# PR9019.net
KiCad netlist of a schematic drawn in EAGLE
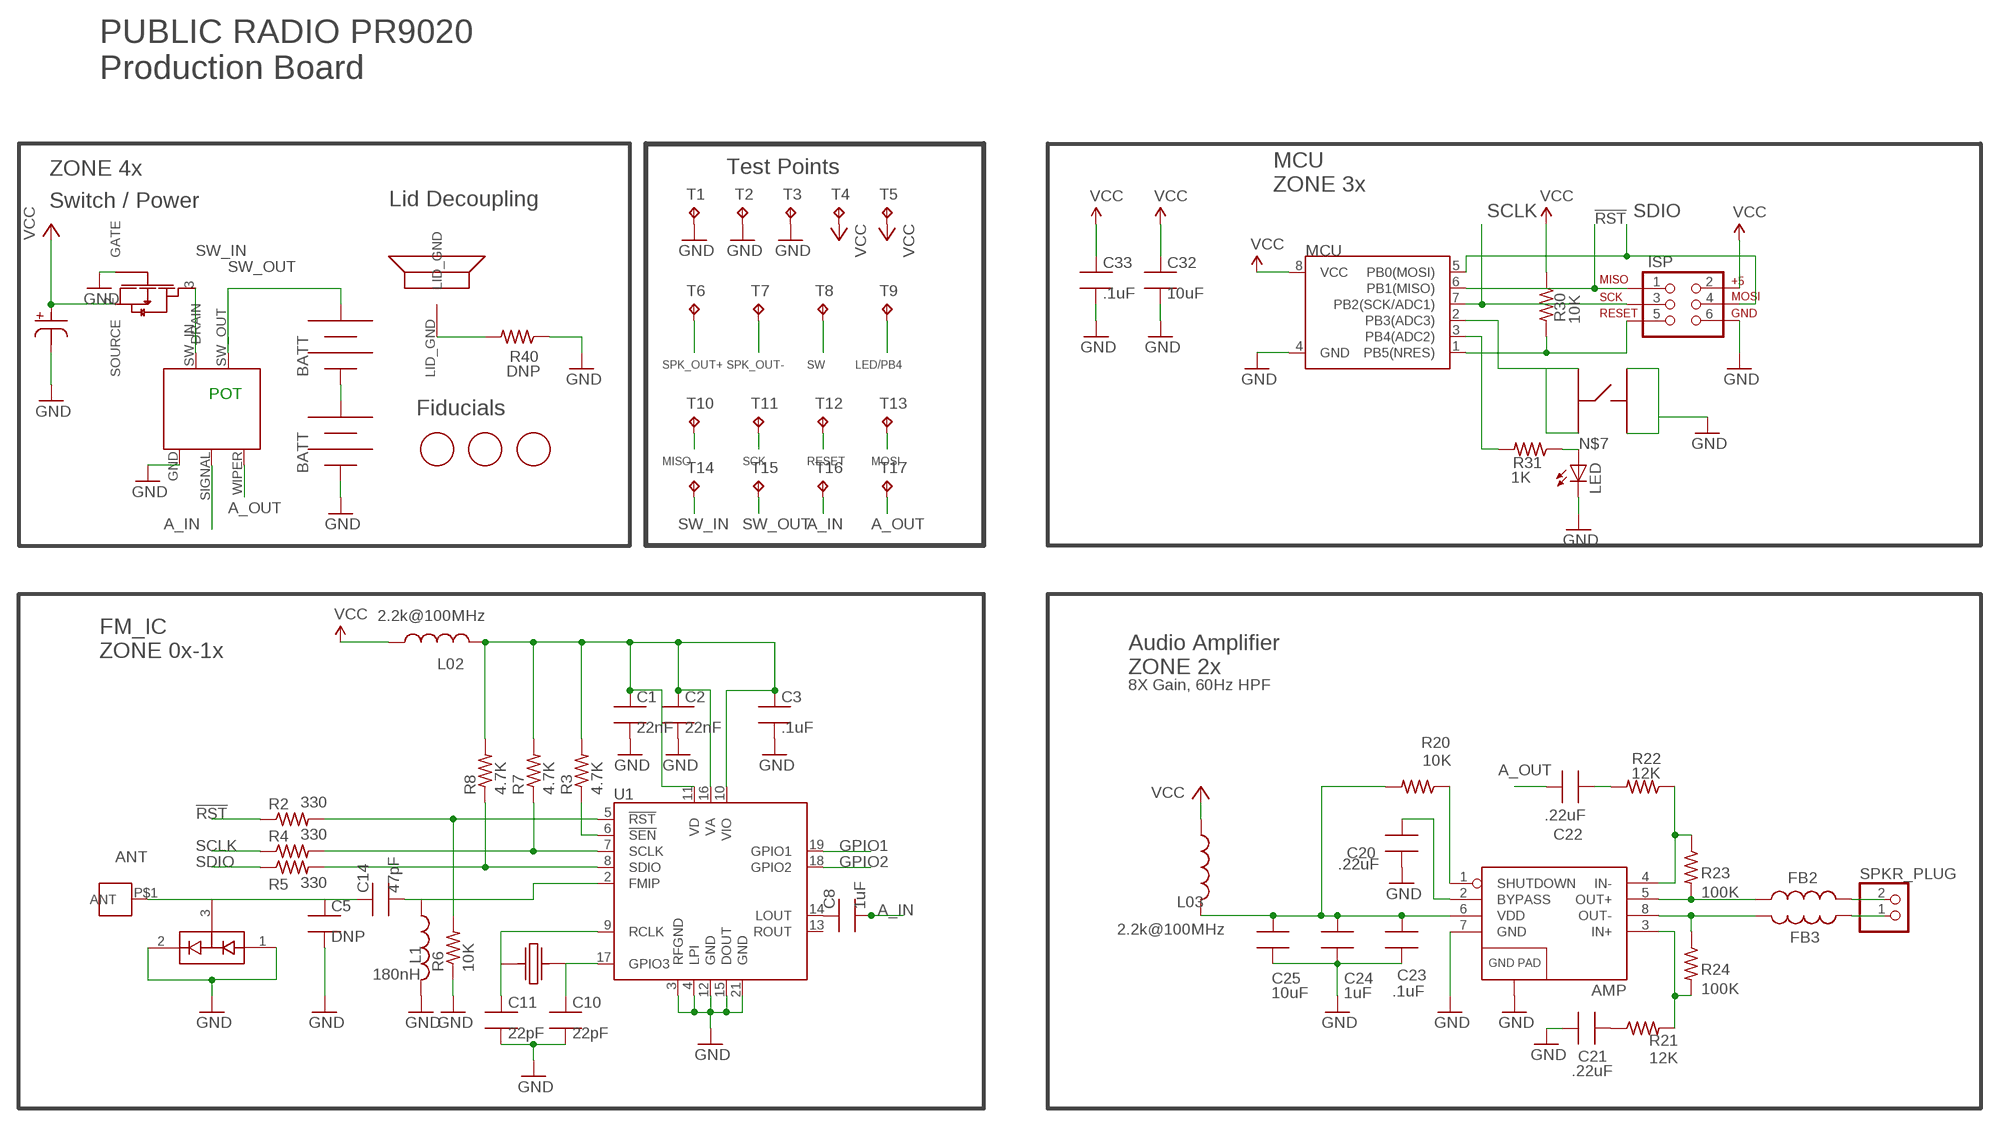
[diagram p0: schematic, sheet 1]

(export (version "E")
  (design (tool "Eeschema 10.0.6"))
  (components
    (comp (ref "AMP")
      (value "TPA6203A1")
      (footprint "eagle-import:8-MSOP")
      (libsource (lib "eagle-import") (part "TPA6203A1"))
    )
    (comp (ref "ANT_MOUNT")
      (value "DNP")
      (footprint "eagle-import:M3_BOLT_HOLE")
      (libsource (lib "eagle-import") (part "M3_SCREW_POST"))
    )
    (comp (ref "C1")
      (value "22nF")
      (footprint "eagle-import:0603_CPL")
      (fields
        (field (name "MFG_PN") "CL10B223KB8NNNC")
        (field (name "TOL") "10%")
        (field (name "VOLTAGE") "16V")
      )
      (libsource (lib "eagle-import") (part "C_SMT_0603_CPL"))
    )
    (comp (ref "C2")
      (value "22nF")
      (footprint "eagle-import:0603_CPL")
      (fields
        (field (name "MFG_PN") "CL10B223KB8NNNC")
        (field (name "TOL") "10%")
        (field (name "VOLTAGE") "16V")
      )
      (libsource (lib "eagle-import") (part "C_SMT_0603_CPL"))
    )
    (comp (ref "C3")
      (value ".1uF")
      (footprint "eagle-import:0603_CPL")
      (fields
        (field (name "MFG_PN") "CL10B104KB8SFNC")
        (field (name "TOL") "10%")
        (field (name "VOLTAGE") "16V")
      )
      (libsource (lib "eagle-import") (part "C_SMT_0603_CPL"))
    )
    (comp (ref "C5")
      (value "DNP")
      (footprint "eagle-import:0603_CPL")
      (fields (field (name "MFG_PN") "DNP") (field (name "TOL") "2%") (field (name "VOLTAGE") "50V"))
      (libsource (lib "eagle-import") (part "C_SMT_0603_CPL"))
    )
    (comp (ref "C8")
      (value "1uF")
      (footprint "eagle-import:0603_CPL")
      (fields
        (field (name "MFG_PN") "CL10B105KP8NNNC")
        (field (name "TOL") "10%")
        (field (name "VOLTAGE") "10V")
      )
      (libsource (lib "eagle-import") (part "C_SMT_0603_CPL"))
    )
    (comp (ref "C10")
      (value "22pF")
      (footprint "eagle-import:0603_CPL")
      (fields
        (field (name "MFG_PN") "C1608C0G1H220J080AA")
        (field (name "TOL") "5%")
        (field (name "VOLTAGE") "50V")
      )
      (libsource (lib "eagle-import") (part "C_SMT_0603_CPL"))
    )
    (comp (ref "C11")
      (value "22pF")
      (footprint "eagle-import:0603_CPL")
      (fields
        (field (name "MFG_PN") "C1608C0G1H220J080AA")
        (field (name "TOL") "5%")
        (field (name "VOLTAGE") "50V")
      )
      (libsource (lib "eagle-import") (part "C_SMT_0603_CPL"))
    )
    (comp (ref "C14")
      (value "47pF")
      (footprint "eagle-import:0603_CPL")
      (fields
        (field (name "MFG_PN") "CL10C470JB8NCNC")
        (field (name "TOL") "5%")
        (field (name "VOLTAGE") "50V")
      )
      (libsource (lib "eagle-import") (part "C_SMT_0603_CPL"))
    )
    (comp (ref "C20")
      (value ".22uF")
      (footprint "eagle-import:0603_CPL")
      (fields
        (field (name "MFG_PN") "C1608X7R1C224K080AC")
        (field (name "TOL") "10%")
        (field (name "VOLTAGE") "16V")
      )
      (libsource (lib "eagle-import") (part "C_SMT_0603_CPL"))
    )
    (comp (ref "C21")
      (value ".22uF")
      (footprint "eagle-import:0603_CPL")
      (fields
        (field (name "MFG_PN") "C1608X7R1C224K080AC")
        (field (name "TOL") "10%")
        (field (name "VOLTAGE") "16V")
      )
      (libsource (lib "eagle-import") (part "C_SMT_0603_CPL"))
    )
    (comp (ref "C22")
      (value ".22uF")
      (footprint "eagle-import:0603_CPL")
      (fields
        (field (name "MFG_PN") "C1608X7R1C224K080AC")
        (field (name "TOL") "10%")
        (field (name "VOLTAGE") "16V")
      )
      (libsource (lib "eagle-import") (part "C_SMT_0603_CPL"))
    )
    (comp (ref "C23")
      (value ".1uF")
      (footprint "eagle-import:0603_CPL")
      (fields
        (field (name "MFG_PN") "CL10B104KB8SFNC")
        (field (name "TOL") "10%")
        (field (name "VOLTAGE") "16V")
      )
      (libsource (lib "eagle-import") (part "C_SMT_0603_CPL"))
    )
    (comp (ref "C24")
      (value "1uF")
      (footprint "eagle-import:0603_CPL")
      (fields
        (field (name "MFG_PN") "CL10B105KP8NNNC")
        (field (name "TOL") "10%")
        (field (name "VOLTAGE") "10V")
      )
      (libsource (lib "eagle-import") (part "C_SMT_0603_CPL"))
    )
    (comp (ref "C25")
      (value "10uF")
      (footprint "eagle-import:0603_CPL")
      (fields
        (field (name "MFG_PN") "CL10A106MQ8NNNC")
        (field (name "TOL") "20%")
        (field (name "VOLTAGE") "6.3V")
      )
      (libsource (lib "eagle-import") (part "C_SMT_0603_CPL"))
    )
    (comp (ref "C32")
      (value "10uF")
      (footprint "eagle-import:0603_CPL")
      (fields
        (field (name "MFG_PN") "CL10A106MQ8NNNC")
        (field (name "TOL") "20%")
        (field (name "VOLTAGE") "6.3V")
      )
      (libsource (lib "eagle-import") (part "C_SMT_0603_CPL"))
    )
    (comp (ref "C33")
      (value ".1uF")
      (footprint "eagle-import:0603_CPL")
      (fields
        (field (name "MFG_PN") "CL10B104KB8SFNC")
        (field (name "TOL") "10%")
        (field (name "VOLTAGE") "16V")
      )
      (libsource (lib "eagle-import") (part "C_SMT_0603_CPL"))
    )
    (comp (ref "C40")
      (value "220uF")
      (footprint "eagle-import:NICHICON_UD_63")
      (fields (field (name "TOL") "20%") (field (name "VOLTAGE") "16V"))
      (libsource (lib "eagle-import") (part "NICHICON_SERIESUD"))
    )
    (comp (ref "D1")
      (value "BAV99")
      (footprint "eagle-import:SOT23_CPL")
      (fields (field (name "MFG_PN") "BAV99,215"))
      (libsource (lib "eagle-import") (part "BAV99"))
    )
    (comp (ref "FB2")
      (value "L_SMT_0805_ADAFRUIT")
      (footprint "eagle-import:0805_ADAFRUIT")
      (fields
        (field (name "CURRENT") "2A")
        (field (name "DCR") "45m")
        (field (name "MFG_PN") "HI0805R800R-10")
      )
      (libsource (lib "eagle-import") (part "L_SMT_0805_ADAFRUIT"))
    )
    (comp (ref "FB3")
      (value "L_SMT_0805_ADAFRUIT")
      (footprint "eagle-import:0805_ADAFRUIT")
      (fields
        (field (name "CURRENT") "2A")
        (field (name "DCR") "45m")
        (field (name "MFG_PN") "HI0805R800R-10")
      )
      (libsource (lib "eagle-import") (part "L_SMT_0805_ADAFRUIT"))
    )
    (comp (ref "FET1")
      (value "AO3435")
      (footprint "eagle-import:SOT23_CPL")
      (fields (field (name "MFG_PN") "AO3435"))
      (libsource (lib "eagle-import") (part "AO3435"))
    )
    (comp (ref "ISP")
      (value "AVR_SPI_PRG_6NS")
      (footprint "eagle-import:2X3-NS")
      (libsource (lib "eagle-import") (part "AVR_SPI_PRG_6NS"))
    )
    (comp (ref "JP5")
      (value "BK-92_MPD_AA_BATT_CLIP")
      (footprint "eagle-import:BK92_AA_BATT")
      (fields (field (name "MFG_PN") "2 of BK92 - supplied by CL Labs"))
      (libsource (lib "eagle-import") (part "BK-92_MPD_AA_BATT_CLIP"))
    )
    (comp (ref "JP6")
      (value "BK-92_MPD_AA_BATT_CLIP")
      (footprint "eagle-import:BK92_AA_BATT")
      (fields (field (name "MFG_PN") "2 of BK92 - supplied by CL Labs"))
      (libsource (lib "eagle-import") (part "BK-92_MPD_AA_BATT_CLIP"))
    )
    (comp (ref "L1")
      (value "180nH")
      (footprint "eagle-import:0805_ADAFRUIT")
      (fields
        (field (name "CURRENT") "400mA")
        (field (name "DCR") "640m")
        (field (name "MFG_PN") "AISC-0805-R18J-T")
        (field (name "TOL") "5%")
      )
      (libsource (lib "eagle-import") (part "L_SMT_0805_ADAFRUIT"))
    )
    (comp (ref "L02")
      (value "2.2k@100MHz")
      (footprint "eagle-import:0603_CPL")
      (fields
        (field (name "CURRENT") "150mA")
        (field (name "DCR") "2.3")
        (field (name "MFG_PN") "HZ0603A222R-10")
      )
      (libsource (lib "eagle-import") (part "L_SMT_0603_CPL"))
    )
    (comp (ref "L03")
      (value "2.2k@100MHz")
      (footprint "eagle-import:0603_CPL")
      (fields
        (field (name "CURRENT") "150mA")
        (field (name "DCR") "2.3")
        (field (name "MFG_PN") "HZ0603A222R-10")
      )
      (libsource (lib "eagle-import") (part "L_SMT_0603_CPL"))
    )
    (comp (ref "LED")
      (value "LEDCHIPLED_0805")
      (footprint "eagle-import:CHIPLED_0805")
      (libsource (lib "eagle-import") (part "LEDCHIPLED_0805"))
    )
    (comp (ref "MARK1")
      (value "FIDUCIAL")
      (footprint "eagle-import:FIDUCIAL_1MM")
      (libsource (lib "eagle-import") (part "FIDUCIAL"))
    )
    (comp (ref "MARK2")
      (value "FIDUCIAL")
      (footprint "eagle-import:FIDUCIAL_1MM")
      (libsource (lib "eagle-import") (part "FIDUCIAL"))
    )
    (comp (ref "MARK3")
      (value "FIDUCIAL")
      (footprint "eagle-import:FIDUCIAL_1MM")
      (libsource (lib "eagle-import") (part "FIDUCIAL"))
    )
    (comp (ref "MCU")
      (value "ATTINY45TINY45-20-SMT")
      (footprint "eagle-import:8-SOIC")
      (libsource (lib "eagle-import") (part "ATTINY45TINY45-20-SMT"))
    )
    (comp (ref "R1")
      (value "RV170SF_TAIWANA_POT_SW")
      (footprint "eagle-import:RV170SF_SW_POT")
      (fields (field (name "MFG_PN") "RV170SF-43-20F-A10K - supplied by CL Labs"))
      (libsource (lib "eagle-import") (part "RV170SF_TAIWANA_POT_SW"))
    )
    (comp (ref "R2")
      (value "330")
      (footprint "eagle-import:0603_CPL")
      (fields (field (name "MFG_PN") "MCR03ERTJ331") (field (name "POWER") "1/10W") (field (name "TOL") "5%"))
      (libsource (lib "eagle-import") (part "R_SMT_R0603_CPL"))
    )
    (comp (ref "R3")
      (value "4.7K")
      (footprint "eagle-import:0603_CPL")
      (fields
        (field (name "MFG_PN") "ERJ-3EKF4701V")
        (field (name "POWER") "1/10W")
        (field (name "TOL") "1%")
      )
      (libsource (lib "eagle-import") (part "R_SMT_R0603_CPL"))
    )
    (comp (ref "R4")
      (value "330")
      (footprint "eagle-import:0603_CPL")
      (fields (field (name "MFG_PN") "MCR03ERTJ331") (field (name "POWER") "1/10W") (field (name "TOL") "5%"))
      (libsource (lib "eagle-import") (part "R_SMT_R0603_CPL"))
    )
    (comp (ref "R5")
      (value "330")
      (footprint "eagle-import:0603_CPL")
      (fields (field (name "MFG_PN") "MCR03ERTJ331") (field (name "POWER") "1/10W") (field (name "TOL") "5%"))
      (libsource (lib "eagle-import") (part "R_SMT_R0603_CPL"))
    )
    (comp (ref "R6")
      (value "10K")
      (footprint "eagle-import:0603_CPL")
      (fields
        (field (name "MFG_PN") "ERJ-3GEYJ103V")
        (field (name "POWER") "1/10W")
        (field (name "TOL") "5%")
      )
      (libsource (lib "eagle-import") (part "R_SMT_R0603_CPL"))
    )
    (comp (ref "R7")
      (value "4.7K")
      (footprint "eagle-import:0603_CPL")
      (fields
        (field (name "MFG_PN") "ERJ-3EKF4701V")
        (field (name "POWER") "1/10W")
        (field (name "TOL") "1%")
      )
      (libsource (lib "eagle-import") (part "R_SMT_R0603_CPL"))
    )
    (comp (ref "R8")
      (value "4.7K")
      (footprint "eagle-import:0603_CPL")
      (fields
        (field (name "MFG_PN") "ERJ-3EKF4701V")
        (field (name "POWER") "1/10W")
        (field (name "TOL") "1%")
      )
      (libsource (lib "eagle-import") (part "R_SMT_R0603_CPL"))
    )
    (comp (ref "R20")
      (value "10K")
      (footprint "eagle-import:0603_CPL")
      (fields
        (field (name "MFG_PN") "ERJ-3GEYJ103V")
        (field (name "POWER") "1/10W")
        (field (name "TOL") "5%")
      )
      (libsource (lib "eagle-import") (part "R_SMT_R0603_CPL"))
    )
    (comp (ref "R21")
      (value "12K")
      (footprint "eagle-import:0603_CPL")
      (fields
        (field (name "MFG_PN") "RC0603FR-0712KL")
        (field (name "POWER") "1/10W")
        (field (name "TOL") "1%")
      )
      (libsource (lib "eagle-import") (part "R_SMT_R0603_CPL"))
    )
    (comp (ref "R22")
      (value "12K")
      (footprint "eagle-import:0603_CPL")
      (fields
        (field (name "MFG_PN") "RC0603FR-0712KL")
        (field (name "POWER") "1/10W")
        (field (name "TOL") "1%")
      )
      (libsource (lib "eagle-import") (part "R_SMT_R0603_CPL"))
    )
    (comp (ref "R23")
      (value "100K")
      (footprint "eagle-import:0603_CPL")
      (fields
        (field (name "MFG_PN") "ERJ-3EKF1003V")
        (field (name "POWER") "1/10W")
        (field (name "TOL") "1%")
      )
      (libsource (lib "eagle-import") (part "R_SMT_R0603_CPL"))
    )
    (comp (ref "R24")
      (value "100K")
      (footprint "eagle-import:0603_CPL")
      (fields
        (field (name "MFG_PN") "ERJ-3EKF1003V")
        (field (name "POWER") "1/10W")
        (field (name "TOL") "1%")
      )
      (libsource (lib "eagle-import") (part "R_SMT_R0603_CPL"))
    )
    (comp (ref "R30")
      (value "10K")
      (footprint "eagle-import:0603_CPL")
      (fields
        (field (name "MFG_PN") "ERJ-3GEYJ103V")
        (field (name "POWER") "1/10W")
        (field (name "TOL") "5%")
      )
      (libsource (lib "eagle-import") (part "R_SMT_R0603_CPL"))
    )
    (comp (ref "R31")
      (value "1K")
      (footprint "eagle-import:0603_CPL")
      (fields
        (field (name "MFG_PN") "ERJ-3EKF1001V")
        (field (name "POWER") "1/10W")
        (field (name "TOL") "1%")
      )
      (libsource (lib "eagle-import") (part "R_SMT_R0603_CPL"))
    )
    (comp (ref "R40")
      (value "DNP")
      (footprint "eagle-import:0603_CPL")
      (fields (field (name "MFG_PN") "ERJ-3GEY0R00V"))
      (libsource (lib "eagle-import") (part "R_SMT_R0603_CPL"))
    )
    (comp (ref "SPKR_PLACE")
      (value "DNP")
      (footprint "eagle-import:PR2023_SPKR_PLACE")
      (libsource (lib "eagle-import") (part "PR2023_SPKR"))
    )
    (comp (ref "SPKR_PLUG")
      (value "JST_2PIN-SMT-RA")
      (footprint "eagle-import:JST-B2B-PH-SM4-TB")
      (libsource (lib "eagle-import") (part "JST_2PIN-SMT-RA"))
    )
    (comp (ref "SW1")
      (value "C&K_PTS645")
      (footprint "eagle-import:C&K_PTS645_SMT")
      (libsource (lib "eagle-import") (part "C&K_PTS645"))
    )
    (comp (ref "T1")
      (value "TPTP20R")
      (footprint "eagle-import:TP20R")
      (libsource (lib "eagle-import") (part "TPTP20R"))
    )
    (comp (ref "T2")
      (value "TPTP20R")
      (footprint "eagle-import:TP20R")
      (libsource (lib "eagle-import") (part "TPTP20R"))
    )
    (comp (ref "T3")
      (value "TPTP20R")
      (footprint "eagle-import:TP20R")
      (libsource (lib "eagle-import") (part "TPTP20R"))
    )
    (comp (ref "T4")
      (value "TPTP20R")
      (footprint "eagle-import:TP20R")
      (libsource (lib "eagle-import") (part "TPTP20R"))
    )
    (comp (ref "T5")
      (value "TPTP20R")
      (footprint "eagle-import:TP20R")
      (libsource (lib "eagle-import") (part "TPTP20R"))
    )
    (comp (ref "T6")
      (value "TPTP20R")
      (footprint "eagle-import:TP20R")
      (libsource (lib "eagle-import") (part "TPTP20R"))
    )
    (comp (ref "T7")
      (value "TPTP20R")
      (footprint "eagle-import:TP20R")
      (libsource (lib "eagle-import") (part "TPTP20R"))
    )
    (comp (ref "T8")
      (value "TPTP20R")
      (footprint "eagle-import:TP20R")
      (libsource (lib "eagle-import") (part "TPTP20R"))
    )
    (comp (ref "T9")
      (value "TPTP20R")
      (footprint "eagle-import:TP20R")
      (libsource (lib "eagle-import") (part "TPTP20R"))
    )
    (comp (ref "T10")
      (value "TPTP20R")
      (footprint "eagle-import:TP20R")
      (libsource (lib "eagle-import") (part "TPTP20R"))
    )
    (comp (ref "T11")
      (value "TPTP20R")
      (footprint "eagle-import:TP20R")
      (libsource (lib "eagle-import") (part "TPTP20R"))
    )
    (comp (ref "T12")
      (value "TPTP20R")
      (footprint "eagle-import:TP20R")
      (libsource (lib "eagle-import") (part "TPTP20R"))
    )
    (comp (ref "T13")
      (value "TPTP20R")
      (footprint "eagle-import:TP20R")
      (libsource (lib "eagle-import") (part "TPTP20R"))
    )
    (comp (ref "T14")
      (value "TPTP20R")
      (footprint "eagle-import:TP20R")
      (libsource (lib "eagle-import") (part "TPTP20R"))
    )
    (comp (ref "T15")
      (value "TPTP20R")
      (footprint "eagle-import:TP20R")
      (libsource (lib "eagle-import") (part "TPTP20R"))
    )
    (comp (ref "T16")
      (value "TPTP20R")
      (footprint "eagle-import:TP20R")
      (libsource (lib "eagle-import") (part "TPTP20R"))
    )
    (comp (ref "T17")
      (value "TPTP20R")
      (footprint "eagle-import:TP20R")
      (libsource (lib "eagle-import") (part "TPTP20R"))
    )
    (comp (ref "U1")
      (value "SI4702-C19-GMR")
      (footprint "eagle-import:SI470X_20_QFN")
      (fields (field (name "MFG_PN") "Si4702 C19 GM - supplied by CL Labs"))
      (libsource (lib "eagle-import") (part "SI4702-C19-GMR"))
    )
    (comp (ref "X1")
      (value "ABS25XTAL")
      (footprint "eagle-import:4-SOJ")
      (libsource (lib "eagle-import") (part "ABS25XTAL"))
    )
  )
  (nets
    (net (code "1") (name "/ANT") (class "Default")
      (node (ref "ANT_MOUNT") (pin "P$1") (pinfunction "ANT_P$1") (pintype "bidirectional"))
      (node (ref "C14") (pin "1") (pinfunction "1_1") (pintype "passive"))
      (node (ref "C5") (pin "1") (pinfunction "1_1") (pintype "passive"))
      (node (ref "D1") (pin "3") (pinfunction "COM_3") (pintype "bidirectional"))
    )
    (net (code "2") (name "/A_IN") (class "Default")
      (node (ref "C8") (pin "2") (pinfunction "2_2") (pintype "passive"))
      (node (ref "R1") (pin "SIGNAL") (pinfunction "SIGNAL_SIGNAL") (pintype "bidirectional"))
      (node (ref "T16") (pin "TP") (pinfunction "TP_TP") (pintype "input"))
    )
    (net (code "3") (name "/A_OUT") (class "Default")
      (node (ref "C22") (pin "2") (pinfunction "2_2") (pintype "passive"))
      (node (ref "R1") (pin "WIPER") (pinfunction "WIPER_WIPER") (pintype "bidirectional"))
      (node (ref "T17") (pin "TP") (pinfunction "TP_TP") (pintype "input"))
    )
    (net (code "4") (name "/GPIO1") (class "Default")
      (node (ref "U1") (pin "19") (pinfunction "GPIO1_19") (pintype "bidirectional"))
    )
    (net (code "5") (name "/GPIO2") (class "Default")
      (node (ref "U1") (pin "18") (pinfunction "GPIO2_18") (pintype "bidirectional"))
    )
    (net (code "6") (name "/LED{slash}PB4") (class "Default")
      (node (ref "MCU") (pin "3") (pinfunction "PB4(ADC2)_3") (pintype "bidirectional"))
      (node (ref "R31") (pin "2") (pinfunction "2_2") (pintype "passive"))
      (node (ref "T9") (pin "TP") (pinfunction "TP_TP") (pintype "input"))
    )
    (net (code "7") (name "/N$7") (class "Default")
      (node (ref "LED") (pin "A") (pinfunction "A_A") (pintype "passive"))
      (node (ref "R31") (pin "1") (pinfunction "1_1") (pintype "passive"))
    )
    (net (code "8") (name "/RESET") (class "Default")
      (node (ref "ISP") (pin "5") (pinfunction "5_5") (pintype "passive"))
      (node (ref "MCU") (pin "1") (pinfunction "PB5(NRES)_1") (pintype "bidirectional"))
      (node (ref "R30") (pin "2") (pinfunction "2_2") (pintype "passive"))
      (node (ref "T12") (pin "TP") (pinfunction "TP_TP") (pintype "input"))
    )
    (net (code "9") (name "/SCLK") (class "Default")
      (node (ref "ISP") (pin "3") (pinfunction "3_3") (pintype "passive"))
      (node (ref "MCU") (pin "7") (pinfunction "PB2(SCK/ADC1)_7") (pintype "bidirectional"))
      (node (ref "R4") (pin "1") (pinfunction "1_1") (pintype "passive"))
      (node (ref "T11") (pin "TP") (pinfunction "TP_TP") (pintype "input"))
    )
    (net (code "10") (name "/SDIO") (class "Default")
      (node (ref "ISP") (pin "4") (pinfunction "4_4") (pintype "passive"))
      (node (ref "MCU") (pin "5") (pinfunction "PB0(MOSI)_5") (pintype "bidirectional"))
      (node (ref "R5") (pin "1") (pinfunction "1_1") (pintype "passive"))
      (node (ref "T13") (pin "TP") (pinfunction "TP_TP") (pintype "input"))
    )
    (net (code "11") (name "/SPK_OUT+") (class "Default")
      (node (ref "FB2") (pin "2") (pinfunction "2_2") (pintype "passive"))
      (node (ref "SPKR_PLUG") (pin "2") (pinfunction "1_2") (pintype "passive"))
      (node (ref "T6") (pin "TP") (pinfunction "TP_TP") (pintype "input"))
    )
    (net (code "12") (name "/SPK_OUT-") (class "Default")
      (node (ref "FB3") (pin "1") (pinfunction "1_1") (pintype "passive"))
      (node (ref "SPKR_PLUG") (pin "1") (pinfunction "2_1") (pintype "passive"))
      (node (ref "T7") (pin "TP") (pinfunction "TP_TP") (pintype "input"))
    )
    (net (code "13") (name "/SW") (class "Default")
      (node (ref "MCU") (pin "2") (pinfunction "PB3(ADC3)_2") (pintype "bidirectional"))
      (node (ref "SW1") (pin "P$3") (pinfunction "P$3_P$3") (pintype "bidirectional"))
      (node (ref "SW1") (pin "P$4") (pinfunction "P$4_P$4") (pintype "bidirectional"))
      (node (ref "T8") (pin "TP") (pinfunction "TP_TP") (pintype "input"))
    )
    (net (code "14") (name "/SW_IN") (class "Default")
      (node (ref "FET1") (pin "3") (pinfunction "DRAIN_3") (pintype "bidirectional"))
      (node (ref "R1") (pin "SW_IN") (pinfunction "SW_IN_SW_IN") (pintype "bidirectional"))
      (node (ref "T14") (pin "TP") (pinfunction "TP_TP") (pintype "input"))
    )
    (net (code "15") (name "/SW_OUT") (class "Default")
      (node (ref "JP5") (pin "POS") (pinfunction "POS_POS") (pintype "bidirectional"))
      (node (ref "JP5") (pin "POS@2") (pinfunction "POS_POS@2") (pintype "bidirectional"))
      (node (ref "R1") (pin "SW_OUT") (pinfunction "SW_OUT_SW_OUT") (pintype "bidirectional"))
      (node (ref "T15") (pin "TP") (pinfunction "TP_TP") (pintype "input"))
    )
    (net (code "16") (name "/~{RST}") (class "Default")
      (node (ref "ISP") (pin "1") (pinfunction "1_1") (pintype "passive"))
      (node (ref "MCU") (pin "6") (pinfunction "PB1(MISO)_6") (pintype "bidirectional"))
      (node (ref "R2") (pin "1") (pinfunction "1_1") (pintype "passive"))
      (node (ref "T10") (pin "TP") (pinfunction "TP_TP") (pintype "input"))
    )
    (net (code "17") (name "GND") (class "Default")
      (node (ref "AMP") (pin "7") (pinfunction "GND_7") (pintype "power_in"))
      (node (ref "AMP") (pin "9") (pinfunction "GND_9") (pintype "power_in"))
      (node (ref "C1") (pin "2") (pinfunction "2_2") (pintype "passive"))
      (node (ref "C10") (pin "2") (pinfunction "2_2") (pintype "passive"))
      (node (ref "C11") (pin "2") (pinfunction "2_2") (pintype "passive"))
      (node (ref "C2") (pin "2") (pinfunction "2_2") (pintype "passive"))
      (node (ref "C20") (pin "1") (pinfunction "1_1") (pintype "passive"))
      (node (ref "C21") (pin "1") (pinfunction "1_1") (pintype "passive"))
      (node (ref "C23") (pin "2") (pinfunction "2_2") (pintype "passive"))
      (node (ref "C24") (pin "2") (pinfunction "2_2") (pintype "passive"))
      (node (ref "C25") (pin "2") (pinfunction "2_2") (pintype "passive"))
      (node (ref "C3") (pin "2") (pinfunction "2_2") (pintype "passive"))
      (node (ref "C32") (pin "2") (pinfunction "2_2") (pintype "passive"))
      (node (ref "C33") (pin "2") (pinfunction "2_2") (pintype "passive"))
      (node (ref "C40") (pin "P$2") (pinfunction "P$2_P$2") (pintype "bidirectional"))
      (node (ref "C5") (pin "2") (pinfunction "2_2") (pintype "passive"))
      (node (ref "D1") (pin "1") (pinfunction "A1_1") (pintype "bidirectional"))
      (node (ref "D1") (pin "2") (pinfunction "C2_2") (pintype "bidirectional"))
      (node (ref "FET1") (pin "1") (pinfunction "GATE_1") (pintype "bidirectional"))
      (node (ref "ISP") (pin "6") (pinfunction "6_6") (pintype "passive"))
      (node (ref "JP6") (pin "NEG") (pinfunction "NEG_NEG") (pintype "bidirectional"))
      (node (ref "JP6") (pin "NEG@2") (pinfunction "NEG_NEG@2") (pintype "bidirectional"))
      (node (ref "L1") (pin "2") (pinfunction "2_2") (pintype "passive"))
      (node (ref "LED") (pin "C") (pinfunction "C_C") (pintype "passive"))
      (node (ref "MCU") (pin "4") (pinfunction "GND_4") (pintype "bidirectional"))
      (node (ref "R1") (pin "GND") (pinfunction "GND_GND") (pintype "bidirectional"))
      (node (ref "R40") (pin "1") (pinfunction "1_1") (pintype "passive"))
      (node (ref "R6") (pin "1") (pinfunction "1_1") (pintype "passive"))
      (node (ref "SW1") (pin "P$1") (pinfunction "P$1_P$1") (pintype "bidirectional"))
      (node (ref "SW1") (pin "P$2") (pinfunction "P$2_P$2") (pintype "bidirectional"))
      (node (ref "T1") (pin "TP") (pinfunction "TP_TP") (pintype "input"))
      (node (ref "T2") (pin "TP") (pinfunction "TP_TP") (pintype "input"))
      (node (ref "T3") (pin "TP") (pinfunction "TP_TP") (pintype "input"))
      (node (ref "U1") (pin "12") (pinfunction "GND_12") (pintype "bidirectional"))
      (node (ref "U1") (pin "15") (pinfunction "DOUT_15") (pintype "bidirectional"))
      (node (ref "U1") (pin "21") (pinfunction "GND_21") (pintype "bidirectional"))
      (node (ref "U1") (pin "3") (pinfunction "RFGND_3") (pintype "bidirectional"))
      (node (ref "U1") (pin "4") (pinfunction "LPI_4") (pintype "bidirectional"))
    )
    (net (code "18") (name "Net-(AMP-BYPASS)") (class "Default")
      (node (ref "AMP") (pin "2") (pinfunction "BYPASS_2") (pintype "bidirectional"))
      (node (ref "C20") (pin "2") (pinfunction "2_2") (pintype "passive"))
    )
    (net (code "19") (name "Net-(AMP-IN+)") (class "Default")
      (node (ref "AMP") (pin "3") (pinfunction "IN+_3") (pintype "bidirectional"))
      (node (ref "R21") (pin "2") (pinfunction "2_2") (pintype "passive"))
      (node (ref "R24") (pin "2") (pinfunction "2_2") (pintype "passive"))
    )
    (net (code "20") (name "Net-(AMP-IN-)") (class "Default")
      (node (ref "AMP") (pin "4") (pinfunction "IN-_4") (pintype "bidirectional"))
      (node (ref "R22") (pin "1") (pinfunction "1_1") (pintype "passive"))
      (node (ref "R23") (pin "1") (pinfunction "1_1") (pintype "passive"))
    )
    (net (code "21") (name "Net-(AMP-OUT+)") (class "Default")
      (node (ref "AMP") (pin "5") (pinfunction "OUT+_5") (pintype "bidirectional"))
      (node (ref "FB2") (pin "1") (pinfunction "1_1") (pintype "passive"))
      (node (ref "R23") (pin "2") (pinfunction "2_2") (pintype "passive"))
    )
    (net (code "22") (name "Net-(AMP-OUT-)") (class "Default")
      (node (ref "AMP") (pin "8") (pinfunction "OUT-_8") (pintype "bidirectional"))
      (node (ref "FB3") (pin "2") (pinfunction "2_2") (pintype "passive"))
      (node (ref "R24") (pin "1") (pinfunction "1_1") (pintype "passive"))
    )
    (net (code "23") (name "Net-(AMP-SHUTDOWN)") (class "Default")
      (node (ref "AMP") (pin "1") (pinfunction "SHUTDOWN_1") (pintype "input"))
      (node (ref "R20") (pin "1") (pinfunction "1_1") (pintype "passive"))
    )
    (net (code "24") (name "Net-(AMP-VDD)") (class "Default")
      (node (ref "AMP") (pin "6") (pinfunction "VDD_6") (pintype "power_in"))
      (node (ref "C23") (pin "1") (pinfunction "1_1") (pintype "passive"))
      (node (ref "C24") (pin "1") (pinfunction "1_1") (pintype "passive"))
      (node (ref "C25") (pin "1") (pinfunction "1_1") (pintype "passive"))
      (node (ref "L03") (pin "2") (pinfunction "2_2") (pintype "passive"))
      (node (ref "R20") (pin "2") (pinfunction "2_2") (pintype "passive"))
    )
    (net (code "25") (name "Net-(C21-Pad2)") (class "Default")
      (node (ref "C21") (pin "2") (pinfunction "2_2") (pintype "passive"))
      (node (ref "R21") (pin "1") (pinfunction "1_1") (pintype "passive"))
    )
    (net (code "26") (name "Net-(C22-Pad1)") (class "Default")
      (node (ref "C22") (pin "1") (pinfunction "1_1") (pintype "passive"))
      (node (ref "R22") (pin "2") (pinfunction "2_2") (pintype "passive"))
    )
    (net (code "27") (name "Net-(JP5-NEG-PadNEG@2)") (class "Default")
      (node (ref "JP5") (pin "NEG") (pinfunction "NEG_NEG") (pintype "bidirectional"))
      (node (ref "JP5") (pin "NEG@2") (pinfunction "NEG_NEG@2") (pintype "bidirectional"))
      (node (ref "JP6") (pin "POS") (pinfunction "POS_POS") (pintype "bidirectional"))
      (node (ref "JP6") (pin "POS@2") (pinfunction "POS_POS@2") (pintype "bidirectional"))
    )
    (net (code "28") (name "Net-(R40-Pad2)") (class "Default")
      (node (ref "R40") (pin "2") (pinfunction "2_2") (pintype "passive"))
      (node (ref "SPKR_PLACE") (pin "LID_GND") (pinfunction "LID_GND_LID_GND") (pintype "bidirectional"))
    )
    (net (code "29") (name "Net-(U1-FMIP)") (class "Default")
      (node (ref "C14") (pin "2") (pinfunction "2_2") (pintype "passive"))
      (node (ref "L1") (pin "1") (pinfunction "1_1") (pintype "passive"))
      (node (ref "U1") (pin "2") (pinfunction "FMIP_2") (pintype "bidirectional"))
    )
    (net (code "30") (name "Net-(U1-GPIO3)") (class "Default")
      (node (ref "C10") (pin "1") (pinfunction "1_1") (pintype "passive"))
      (node (ref "U1") (pin "17") (pinfunction "GPIO3_17") (pintype "bidirectional"))
      (node (ref "X1") (pin "P$4") (pinfunction "P$4_P$4") (pintype "bidirectional"))
    )
    (net (code "31") (name "Net-(U1-LOUT)") (class "Default")
      (node (ref "C8") (pin "1") (pinfunction "1_1") (pintype "passive"))
      (node (ref "U1") (pin "14") (pinfunction "LOUT_14") (pintype "bidirectional"))
    )
    (net (code "32") (name "Net-(U1-RCLK)") (class "Default")
      (node (ref "C11") (pin "1") (pinfunction "1_1") (pintype "passive"))
      (node (ref "U1") (pin "9") (pinfunction "RCLK_9") (pintype "bidirectional"))
      (node (ref "X1") (pin "P$1") (pinfunction "P$1_P$1") (pintype "bidirectional"))
    )
    (net (code "33") (name "Net-(U1-SCLK)") (class "Default")
      (node (ref "R4") (pin "2") (pinfunction "2_2") (pintype "passive"))
      (node (ref "R7") (pin "1") (pinfunction "1_1") (pintype "passive"))
      (node (ref "U1") (pin "7") (pinfunction "SCLK_7") (pintype "bidirectional"))
    )
    (net (code "34") (name "Net-(U1-SDIO)") (class "Default")
      (node (ref "R5") (pin "2") (pinfunction "2_2") (pintype "passive"))
      (node (ref "R8") (pin "1") (pinfunction "1_1") (pintype "passive"))
      (node (ref "U1") (pin "8") (pinfunction "SDIO_8") (pintype "bidirectional"))
    )
    (net (code "35") (name "Net-(U1-VA)") (class "Default")
      (node (ref "C1") (pin "1") (pinfunction "1_1") (pintype "passive"))
      (node (ref "C2") (pin "1") (pinfunction "1_1") (pintype "passive"))
      (node (ref "C3") (pin "1") (pinfunction "1_1") (pintype "passive"))
      (node (ref "L02") (pin "2") (pinfunction "2_2") (pintype "passive"))
      (node (ref "R3") (pin "2") (pinfunction "2_2") (pintype "passive"))
      (node (ref "R7") (pin "2") (pinfunction "2_2") (pintype "passive"))
      (node (ref "R8") (pin "2") (pinfunction "2_2") (pintype "passive"))
      (node (ref "U1") (pin "10") (pinfunction "VIO_10") (pintype "bidirectional"))
      (node (ref "U1") (pin "11") (pinfunction "VD_11") (pintype "bidirectional"))
      (node (ref "U1") (pin "16") (pinfunction "VA_16") (pintype "bidirectional"))
    )
    (net (code "36") (name "Net-(U1-~{RST})") (class "Default")
      (node (ref "R2") (pin "2") (pinfunction "2_2") (pintype "passive"))
      (node (ref "R6") (pin "2") (pinfunction "2_2") (pintype "passive"))
      (node (ref "U1") (pin "5") (pinfunction "~{RST}_5") (pintype "bidirectional"))
    )
    (net (code "37") (name "Net-(U1-~{SEN})") (class "Default")
      (node (ref "R3") (pin "1") (pinfunction "1_1") (pintype "passive"))
      (node (ref "U1") (pin "6") (pinfunction "~{SEN}_6") (pintype "bidirectional"))
    )
    (net (code "38") (name "VCC") (class "Default")
      (node (ref "C32") (pin "1") (pinfunction "1_1") (pintype "passive"))
      (node (ref "C33") (pin "1") (pinfunction "1_1") (pintype "passive"))
      (node (ref "C40") (pin "P$1") (pinfunction "P$1_P$1") (pintype "bidirectional"))
      (node (ref "FET1") (pin "2") (pinfunction "SOURCE_2") (pintype "bidirectional"))
      (node (ref "ISP") (pin "2") (pinfunction "2_2") (pintype "passive"))
      (node (ref "L02") (pin "1") (pinfunction "1_1") (pintype "passive"))
      (node (ref "L03") (pin "1") (pinfunction "1_1") (pintype "passive"))
      (node (ref "MCU") (pin "8") (pinfunction "VCC_8") (pintype "bidirectional"))
      (node (ref "R30") (pin "1") (pinfunction "1_1") (pintype "passive"))
      (node (ref "T4") (pin "TP") (pinfunction "TP_TP") (pintype "input"))
      (node (ref "T5") (pin "TP") (pinfunction "TP_TP") (pintype "input"))
    )
    (net (code "39") (name "unconnected-(U1-ROUT-Pad13)") (class "Default")
      (node (ref "U1") (pin "13") (pinfunction "ROUT_13") (pintype "bidirectional"))
    )
  )
)
